# Power.net
KiCad netlist of a schematic drawn in Altium Designer
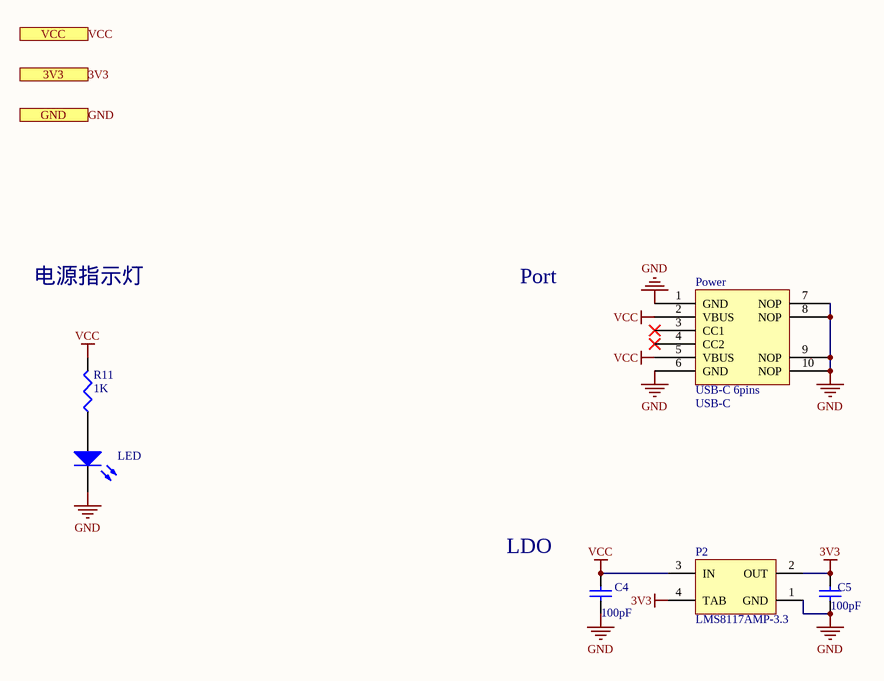
[diagram p0: Power.SchDoc]

(export (version "E")
  (design (tool "Eeschema 10.0.6"))
  (components
    (comp (ref "C4")
      (value "100pF")
      (footprint "6-0805_N")
      (description "Capacitor")
      (fields (field (name "Comment") "Cap") (field (name "PUBLISHER") "Altium Limited"))
      (libsource (lib "Miscellaneous Devices") (part "Cap"))
    )
    (comp (ref "C5")
      (value "100pF")
      (footprint "6-0805_N")
      (description "Capacitor")
      (fields (field (name "Comment") "Cap") (field (name "PUBLISHER") "Altium Limited"))
      (libsource (lib "Miscellaneous Devices") (part "Cap"))
    )
    (comp (ref "LED")
      (value "LED3")
      (footprint "Miscellaneous Devices:6-0805_N")
      (description "Typical BLUE SiC LED")
      (fields (field (name "PUBLISHER") "Altium Limited"))
      (libsource (lib "Miscellaneous Devices") (part "LED3"))
    )
    (comp (ref "P2")
      (value "LMS8117AMP-3.3")
      (footprint "MP04A_N")
      (description "1A Low-Dropout Linear Regulator, 4-pin SOT-223")
      (fields (field (name "MANUFACTURER") "National Semiconductor"))
      (libsource (lib "National Semiconductor LDO") (part "LMS8117AMP-3.3"))
    )
    (comp (ref "Power") (value "USB-C") (footprint "USB-C") (libsource (lib "USB") (part "USB-C")))
    (comp (ref "R11")
      (value "1K")
      (footprint "6-0805_N")
      (description "Resistor")
      (fields (field (name "Comment") "Res3") (field (name "PUBLISHER") "Altium Limited"))
      (libsource (lib "Miscellaneous Devices") (part "Res3"))
    )
  )
  (nets
    (net (code "1") (name "3V3") (class "Default")
      (node (ref "C5") (pin "2") (pinfunction "2_2") (pintype "passive"))
      (node (ref "P2") (pin "2") (pinfunction "OUT_2") (pintype "power_in"))
      (node (ref "P2") (pin "4") (pinfunction "TAB_4") (pintype "power_in"))
    )
    (net (code "2") (name "GND") (class "Default")
      (node (ref "C4") (pin "1") (pinfunction "1_1") (pintype "passive"))
      (node (ref "C5") (pin "1") (pinfunction "1_1") (pintype "passive"))
      (node (ref "LED") (pin "2") (pinfunction "K_2") (pintype "passive"))
      (node (ref "P2") (pin "1") (pinfunction "GND_1") (pintype "power_in"))
      (node (ref "Power") (pin "1") (pinfunction "GND_1") (pintype "passive"))
      (node (ref "Power") (pin "10") (pinfunction "NOP_10") (pintype "passive"))
      (node (ref "Power") (pin "6") (pinfunction "GND_6") (pintype "passive"))
      (node (ref "Power") (pin "7") (pinfunction "NOP_7") (pintype "passive"))
      (node (ref "Power") (pin "8") (pinfunction "NOP_8") (pintype "passive"))
      (node (ref "Power") (pin "9") (pinfunction "NOP_9") (pintype "passive"))
    )
    (net (code "3") (name "Net-(LED-A)") (class "Default")
      (node (ref "LED") (pin "1") (pinfunction "A_1") (pintype "passive"))
      (node (ref "R11") (pin "1") (pinfunction "1_1") (pintype "passive"))
    )
    (net (code "4") (name "VCC") (class "Default")
      (node (ref "C4") (pin "2") (pinfunction "2_2") (pintype "passive"))
      (node (ref "P2") (pin "3") (pinfunction "IN_3") (pintype "power_in"))
      (node (ref "Power") (pin "2") (pinfunction "VBUS_2") (pintype "passive"))
      (node (ref "Power") (pin "5") (pinfunction "VBUS_5") (pintype "passive"))
      (node (ref "R11") (pin "2") (pinfunction "2_2") (pintype "passive"))
    )
    (net (code "5") (name "unconnected-(Power-CC1-Pad3)") (class "Default")
      (node (ref "Power") (pin "3") (pinfunction "CC1_3") (pintype "passive+no_connect"))
    )
    (net (code "6") (name "unconnected-(Power-CC2-Pad4)") (class "Default")
      (node (ref "Power") (pin "4") (pinfunction "CC2_4") (pintype "passive+no_connect"))
    )
  )
)
